# Connectors.net
KiCad netlist of a schematic drawn in Altium Designer
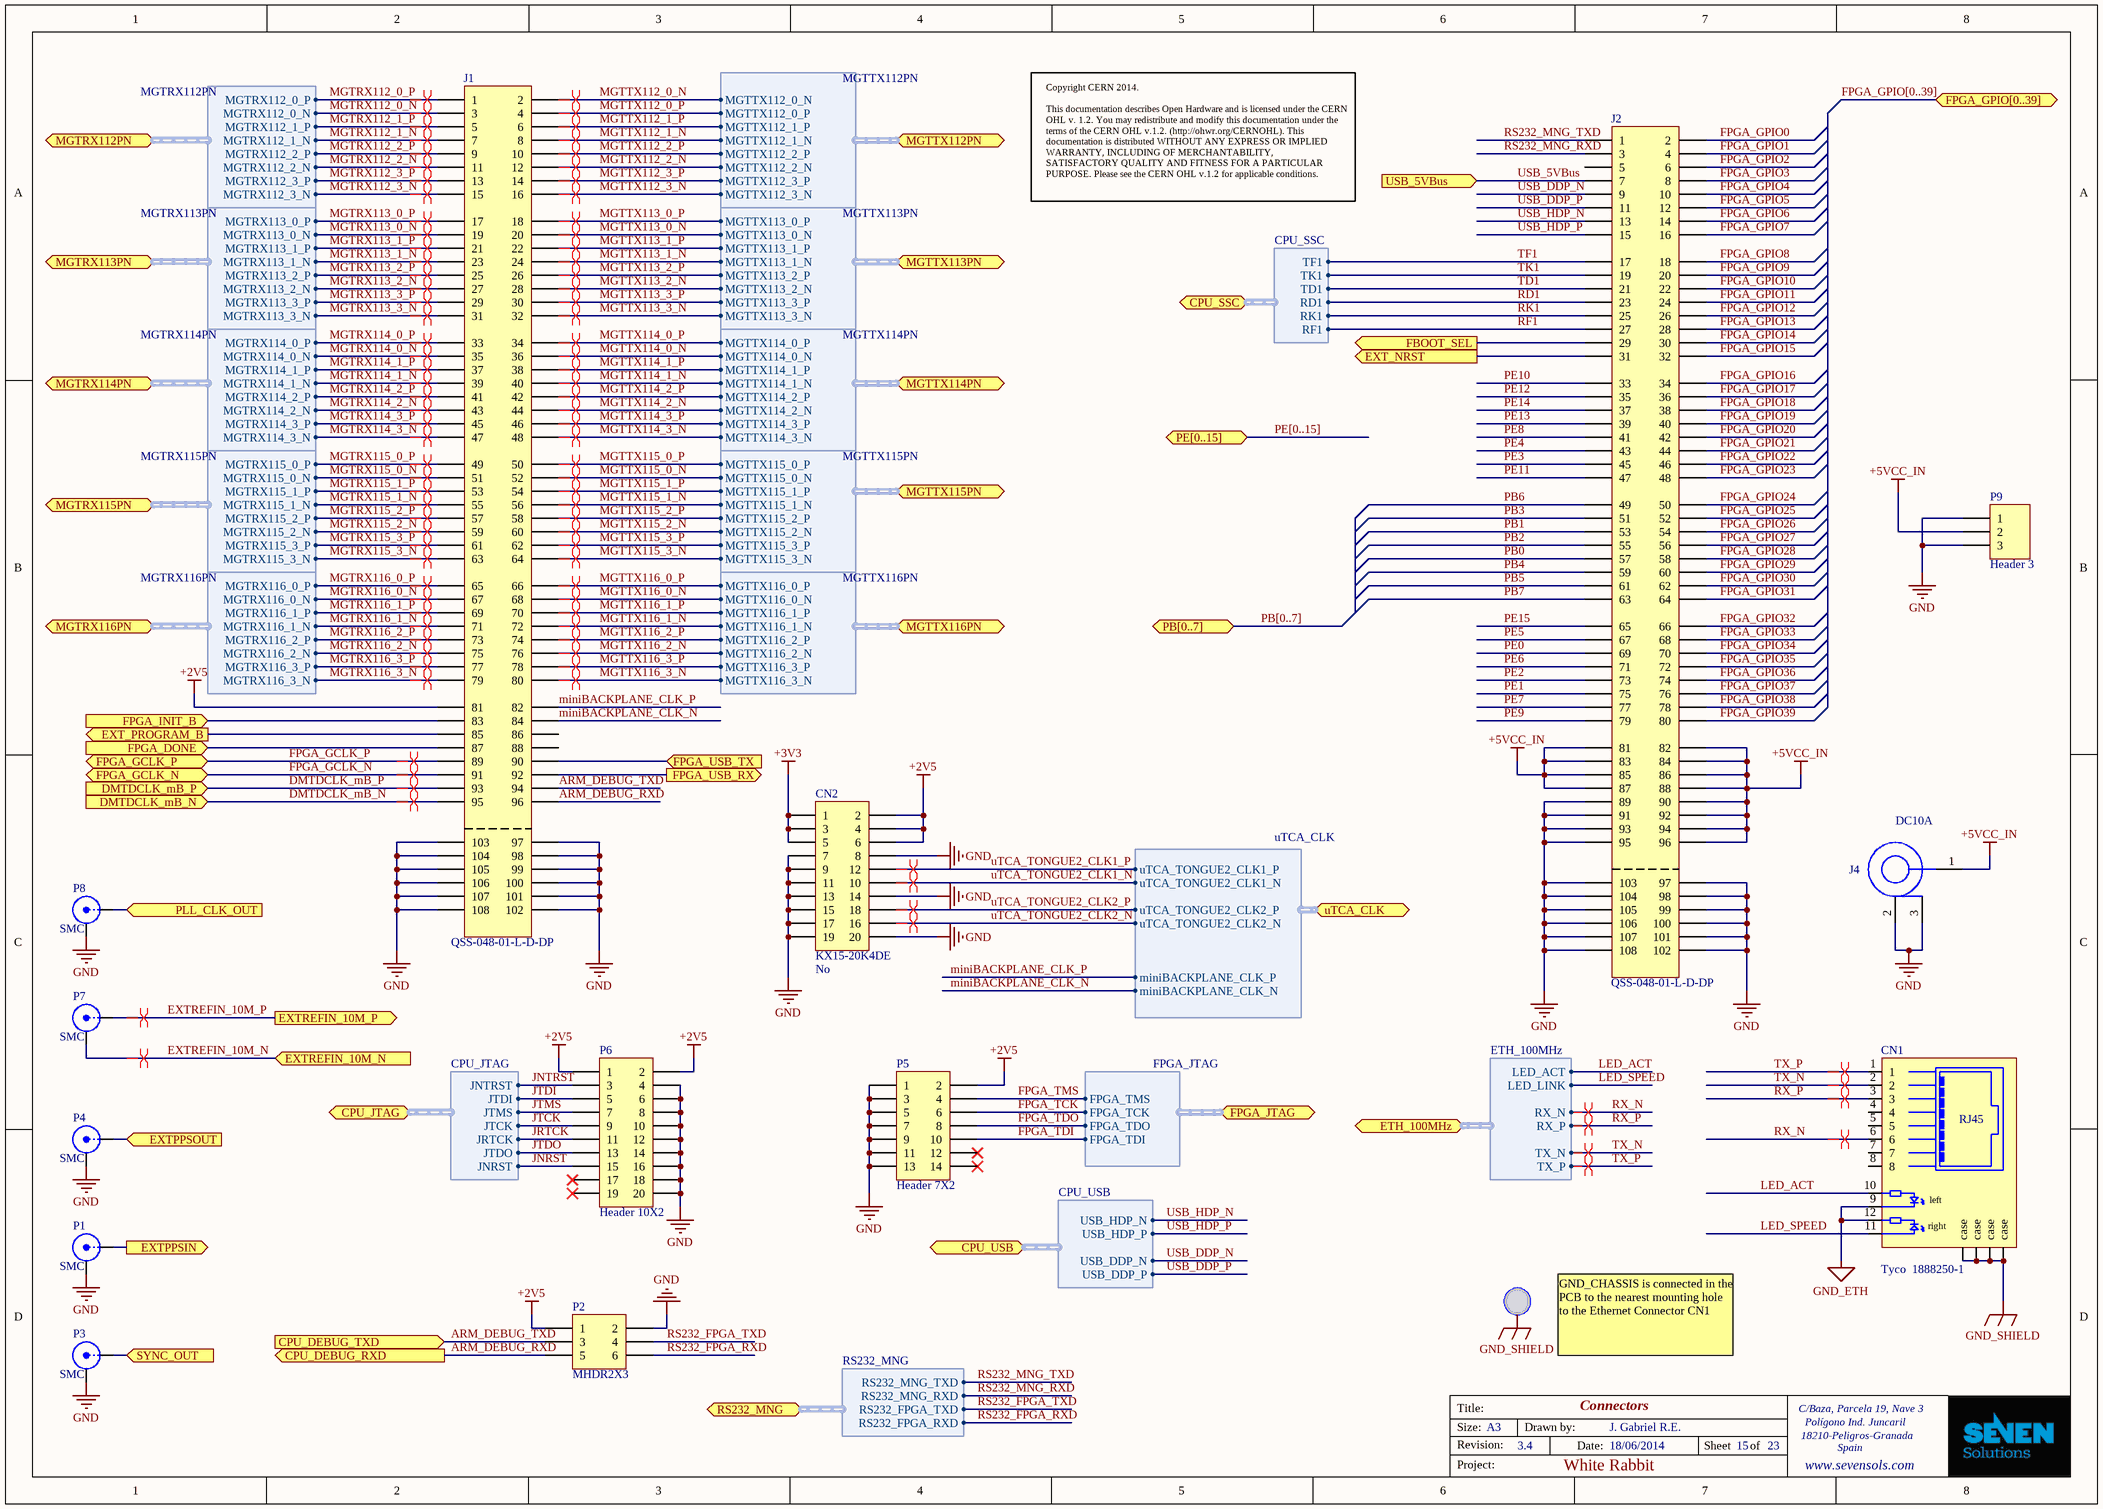
[diagram p0: Connectors.SchDoc]

(export (version "E")
  (design (tool "Eeschema 10.0.6"))
  (components
    (comp (ref "CN1")
      (value "Tyco  1888250-1")
      (footprint "TYCO_ETHERNET_1888250-1")
      (description "low profile uTCA Ethernet jack (RJ45)")
      (libsource (lib "wr_switch") (part "CON_ETHERNET_TYCO_1888250-1"))
    )
    (comp (ref "CN2")
      (value "KX15-20K4DE")
      (footprint "JAE_KX15_20P")
      (description "multipin B2B connector (plug)")
      (fields (field (name "MOUNTED") "No"))
      (libsource (lib "wr_switch") (part "KX15_20p"))
    )
    (comp (ref "J1")
      (value "QSS-048-01-L-D-DP")
      (footprint "QSS-048-01-X-D-DP-A")
      (libsource (lib "wr_switch") (part "QSS-048-01-L-D-DP"))
    )
    (comp (ref "J2")
      (value "QSS-048-01-L-D-DP")
      (footprint "QSS-048-01-X-D-DP-A")
      (description "High Speed Ground Plane Header")
      (libsource (lib "wr_switch") (part "QSS-048-01-L-D-DP"))
    )
    (comp (ref "J4")
      (value "DC10A")
      (footprint "dc-10")
      (description "Power Jack 5A @ 12V")
      (libsource (lib "wr_switch") (part "PWR_JACK"))
    )
    (comp (ref "P1")
      (value "SMC")
      (footprint "SMB_V-RJ45")
      (description "SMB Straight Connector")
      (fields (field (name "PUBLISHER") "Altium Limited"))
      (libsource (lib "Miscellaneous Connectors") (part "SMB"))
    )
    (comp (ref "P2")
      (value "MHDR2X3")
      (footprint "7S_WR:HDR2x3_M22")
      (description "SMD Header, 3-Pin, Dual row, 2.54mm pitch")
      (libsource (lib "Miscellaneous Connectors") (part "MHDR2X3"))
    )
    (comp (ref "P3")
      (value "SMC")
      (footprint "SMB_V-RJ45")
      (description "SMB Straight Connector")
      (fields (field (name "PUBLISHER") "Altium Limited"))
      (libsource (lib "Miscellaneous Connectors") (part "SMB"))
    )
    (comp (ref "P4")
      (value "SMC")
      (footprint "SMB_V-RJ45")
      (description "SMB Straight Connector")
      (fields (field (name "PUBLISHER") "Altium Limited"))
      (libsource (lib "Miscellaneous Connectors") (part "SMB"))
    )
    (comp (ref "P5")
      (value "Header 7X2")
      (footprint "7S_WR:CONN_HDR_SMD_2mm_2x7")
      (description "Header, 7-Pin, Dual row, 2.0 mm pitch")
      (fields (field (name "PUBLISHER") "Altium Limited"))
      (libsource (lib "Miscellaneous Connectors") (part "Header 7X2"))
    )
    (comp (ref "P6")
      (value "Header 10X2")
      (footprint "7S_WR:HDR2X10_SBH11")
      (description "Header, 10-Pin, Dual row, 2.54mm pitch")
      (fields (field (name "MANUFACTURER") "Sullis Connectors") (field (name "PUBLISHER") "Altium Limited"))
      (libsource (lib "Miscellaneous Connectors") (part "Header 10X2"))
    )
    (comp (ref "P7")
      (value "SMC")
      (footprint "SMB_V-RJ45")
      (description "SMB Straight Connector")
      (fields (field (name "PUBLISHER") "Altium Limited"))
      (libsource (lib "Miscellaneous Connectors") (part "SMB"))
    )
    (comp (ref "P8")
      (value "SMC")
      (footprint "SMB_V-RJ45")
      (description "SMB Straight Connector")
      (fields (field (name "PUBLISHER") "Altium Limited"))
      (libsource (lib "Miscellaneous Connectors") (part "SMB"))
    )
    (comp (ref "P9")
      (value "Header 3")
      (footprint "7S_WR:HDR1x3_BG055")
      (description "Header, 3-Pin")
      (fields (field (name "PUBLISHER") "Altium Limited"))
      (libsource (lib "Miscellaneous Connectors") (part "Header 3"))
    )
  )
  (nets
    (net (code "18") (name "+2V5") (class "Default")
      (node (ref "CN2") (pin "2") (pinfunction "2_2") (pintype "passive"))
      (node (ref "CN2") (pin "4") (pinfunction "4_4") (pintype "passive"))
      (node (ref "CN2") (pin "6") (pinfunction "6_6") (pintype "passive"))
      (node (ref "J1") (pin "81") (pinfunction "81_81") (pintype "passive"))
      (node (ref "P2") (pin "1") (pinfunction "1_1") (pintype "passive"))
      (node (ref "P5") (pin "2") (pinfunction "2_2") (pintype "passive"))
      (node (ref "P6") (pin "1") (pinfunction "1_1") (pintype "passive"))
      (node (ref "P6") (pin "2") (pinfunction "2_2") (pintype "passive"))
    )
    (net (code "19") (name "+3V3") (class "Default")
      (node (ref "CN2") (pin "1") (pinfunction "1_1") (pintype "passive"))
      (node (ref "CN2") (pin "3") (pinfunction "3_3") (pintype "passive"))
      (node (ref "CN2") (pin "5") (pinfunction "5_5") (pintype "passive"))
    )
    (net (code "20") (name "+5VCC_IN") (class "Default")
      (node (ref "J2") (pin "81") (pinfunction "81_81") (pintype "passive"))
      (node (ref "J2") (pin "82") (pinfunction "82_82") (pintype "passive"))
      (node (ref "J2") (pin "83") (pinfunction "83_83") (pintype "passive"))
      (node (ref "J2") (pin "84") (pinfunction "84_84") (pintype "passive"))
      (node (ref "J2") (pin "85") (pinfunction "85_85") (pintype "passive"))
      (node (ref "J2") (pin "86") (pinfunction "86_86") (pintype "passive"))
      (node (ref "J2") (pin "87") (pinfunction "87_87") (pintype "passive"))
      (node (ref "J2") (pin "88") (pinfunction "88_88") (pintype "passive"))
      (node (ref "J2") (pin "90") (pinfunction "90_90") (pintype "passive"))
      (node (ref "J2") (pin "92") (pinfunction "92_92") (pintype "passive"))
      (node (ref "J2") (pin "94") (pinfunction "94_94") (pintype "passive"))
      (node (ref "J2") (pin "96") (pinfunction "96_96") (pintype "passive"))
      (node (ref "J4") (pin "1") (pinfunction "P1_1") (pintype "power_in"))
      (node (ref "P9") (pin "2") (pinfunction "2_2") (pintype "passive"))
    )
    (net (code "21") (name "/ARM_DEBUG_RXD") (class "Default")
      (node (ref "J1") (pin "96") (pinfunction "96_96") (pintype "passive"))
      (node (ref "P2") (pin "5") (pinfunction "5_5") (pintype "passive"))
    )
    (net (code "22") (name "/ARM_DEBUG_TXD") (class "Default")
      (node (ref "J1") (pin "94") (pinfunction "94_94") (pintype "passive"))
      (node (ref "P2") (pin "3") (pinfunction "3_3") (pintype "passive"))
    )
    (net (code "23") (name "/DMTDCLK_mB_N") (class "Default")
      (node (ref "J1") (pin "95") (pinfunction "95_95") (pintype "passive"))
    )
    (net (code "24") (name "/DMTDCLK_mB_P") (class "Default")
      (node (ref "J1") (pin "93") (pinfunction "93_93") (pintype "passive"))
    )
    (net (code "25") (name "/EXTPPSIN") (class "Default")
      (node (ref "P1") (pin "1") (pinfunction "X_1") (pintype "passive"))
    )
    (net (code "26") (name "/EXTPPSOUT") (class "Default")
      (node (ref "P4") (pin "1") (pinfunction "X_1") (pintype "passive"))
    )
    (net (code "27") (name "/EXTREFIN_10M_N") (class "Default")
      (node (ref "P7") (pin "2") (pinfunction "Y_2") (pintype "passive"))
    )
    (net (code "28") (name "/EXTREFIN_10M_P") (class "Default")
      (node (ref "P7") (pin "1") (pinfunction "X_1") (pintype "passive"))
    )
    (net (code "29") (name "/EXT_NRST") (class "Default")
      (node (ref "J2") (pin "31") (pinfunction "31_31") (pintype "passive"))
    )
    (net (code "30") (name "/EXT_PROGRAM_B") (class "Default")
      (node (ref "J1") (pin "85") (pinfunction "85_85") (pintype "passive"))
    )
    (net (code "31") (name "/FBOOT_SEL") (class "Default")
      (node (ref "J2") (pin "29") (pinfunction "29_29") (pintype "passive"))
    )
    (net (code "32") (name "/FPGA_DONE") (class "Default")
      (node (ref "J1") (pin "87") (pinfunction "87_87") (pintype "passive"))
    )
    (net (code "33") (name "/FPGA_GCLK_N") (class "Default")
      (node (ref "J1") (pin "91") (pinfunction "91_91") (pintype "passive"))
    )
    (net (code "34") (name "/FPGA_GCLK_P") (class "Default")
      (node (ref "J1") (pin "89") (pinfunction "89_89") (pintype "passive"))
    )
    (net (code "35") (name "/FPGA_GPIO0") (class "Default")
      (node (ref "J2") (pin "2") (pinfunction "2_2") (pintype "passive"))
    )
    (net (code "36") (name "/FPGA_GPIO1") (class "Default")
      (node (ref "J2") (pin "4") (pinfunction "4_4") (pintype "passive"))
    )
    (net (code "37") (name "/FPGA_GPIO2") (class "Default")
      (node (ref "J2") (pin "6") (pinfunction "6_6") (pintype "passive"))
    )
    (net (code "38") (name "/FPGA_GPIO3") (class "Default")
      (node (ref "J2") (pin "8") (pinfunction "8_8") (pintype "passive"))
    )
    (net (code "39") (name "/FPGA_GPIO4") (class "Default")
      (node (ref "J2") (pin "10") (pinfunction "10_10") (pintype "passive"))
    )
    (net (code "40") (name "/FPGA_GPIO5") (class "Default")
      (node (ref "J2") (pin "12") (pinfunction "12_12") (pintype "passive"))
    )
    (net (code "41") (name "/FPGA_GPIO6") (class "Default")
      (node (ref "J2") (pin "14") (pinfunction "14_14") (pintype "passive"))
    )
    (net (code "42") (name "/FPGA_GPIO7") (class "Default")
      (node (ref "J2") (pin "16") (pinfunction "16_16") (pintype "passive"))
    )
    (net (code "43") (name "/FPGA_GPIO8") (class "Default")
      (node (ref "J2") (pin "18") (pinfunction "18_18") (pintype "passive"))
    )
    (net (code "44") (name "/FPGA_GPIO9") (class "Default")
      (node (ref "J2") (pin "20") (pinfunction "20_20") (pintype "passive"))
    )
    (net (code "45") (name "/FPGA_GPIO10") (class "Default")
      (node (ref "J2") (pin "22") (pinfunction "22_22") (pintype "passive"))
    )
    (net (code "46") (name "/FPGA_GPIO11") (class "Default")
      (node (ref "J2") (pin "24") (pinfunction "24_24") (pintype "passive"))
    )
    (net (code "47") (name "/FPGA_GPIO12") (class "Default")
      (node (ref "J2") (pin "26") (pinfunction "26_26") (pintype "passive"))
    )
    (net (code "48") (name "/FPGA_GPIO13") (class "Default")
      (node (ref "J2") (pin "28") (pinfunction "28_28") (pintype "passive"))
    )
    (net (code "49") (name "/FPGA_GPIO14") (class "Default")
      (node (ref "J2") (pin "30") (pinfunction "30_30") (pintype "passive"))
    )
    (net (code "50") (name "/FPGA_GPIO15") (class "Default")
      (node (ref "J2") (pin "32") (pinfunction "32_32") (pintype "passive"))
    )
    (net (code "51") (name "/FPGA_GPIO16") (class "Default")
      (node (ref "J2") (pin "34") (pinfunction "34_34") (pintype "passive"))
    )
    (net (code "52") (name "/FPGA_GPIO17") (class "Default")
      (node (ref "J2") (pin "36") (pinfunction "36_36") (pintype "passive"))
    )
    (net (code "53") (name "/FPGA_GPIO18") (class "Default")
      (node (ref "J2") (pin "38") (pinfunction "38_38") (pintype "passive"))
    )
    (net (code "54") (name "/FPGA_GPIO19") (class "Default")
      (node (ref "J2") (pin "40") (pinfunction "40_40") (pintype "passive"))
    )
    (net (code "55") (name "/FPGA_GPIO20") (class "Default")
      (node (ref "J2") (pin "42") (pinfunction "42_42") (pintype "passive"))
    )
    (net (code "56") (name "/FPGA_GPIO21") (class "Default")
      (node (ref "J2") (pin "44") (pinfunction "44_44") (pintype "passive"))
    )
    (net (code "57") (name "/FPGA_GPIO22") (class "Default")
      (node (ref "J2") (pin "46") (pinfunction "46_46") (pintype "passive"))
    )
    (net (code "58") (name "/FPGA_GPIO23") (class "Default")
      (node (ref "J2") (pin "48") (pinfunction "48_48") (pintype "passive"))
    )
    (net (code "59") (name "/FPGA_GPIO24") (class "Default")
      (node (ref "J2") (pin "50") (pinfunction "50_50") (pintype "passive"))
    )
    (net (code "60") (name "/FPGA_GPIO25") (class "Default")
      (node (ref "J2") (pin "52") (pinfunction "52_52") (pintype "passive"))
    )
    (net (code "61") (name "/FPGA_GPIO26") (class "Default")
      (node (ref "J2") (pin "54") (pinfunction "54_54") (pintype "passive"))
    )
    (net (code "62") (name "/FPGA_GPIO27") (class "Default")
      (node (ref "J2") (pin "56") (pinfunction "56_56") (pintype "passive"))
    )
    (net (code "63") (name "/FPGA_GPIO28") (class "Default")
      (node (ref "J2") (pin "58") (pinfunction "58_58") (pintype "passive"))
    )
    (net (code "64") (name "/FPGA_GPIO29") (class "Default")
      (node (ref "J2") (pin "60") (pinfunction "60_60") (pintype "passive"))
    )
    (net (code "65") (name "/FPGA_GPIO30") (class "Default")
      (node (ref "J2") (pin "62") (pinfunction "62_62") (pintype "passive"))
    )
    (net (code "66") (name "/FPGA_GPIO31") (class "Default")
      (node (ref "J2") (pin "64") (pinfunction "64_64") (pintype "passive"))
    )
    (net (code "67") (name "/FPGA_GPIO32") (class "Default")
      (node (ref "J2") (pin "66") (pinfunction "66_66") (pintype "passive"))
    )
    (net (code "68") (name "/FPGA_GPIO33") (class "Default")
      (node (ref "J2") (pin "68") (pinfunction "68_68") (pintype "passive"))
    )
    (net (code "69") (name "/FPGA_GPIO34") (class "Default")
      (node (ref "J2") (pin "70") (pinfunction "70_70") (pintype "passive"))
    )
    (net (code "70") (name "/FPGA_GPIO35") (class "Default")
      (node (ref "J2") (pin "72") (pinfunction "72_72") (pintype "passive"))
    )
    (net (code "71") (name "/FPGA_GPIO36") (class "Default")
      (node (ref "J2") (pin "74") (pinfunction "74_74") (pintype "passive"))
    )
    (net (code "72") (name "/FPGA_GPIO37") (class "Default")
      (node (ref "J2") (pin "76") (pinfunction "76_76") (pintype "passive"))
    )
    (net (code "73") (name "/FPGA_GPIO38") (class "Default")
      (node (ref "J2") (pin "78") (pinfunction "78_78") (pintype "passive"))
    )
    (net (code "74") (name "/FPGA_GPIO39") (class "Default")
      (node (ref "J2") (pin "80") (pinfunction "80_80") (pintype "passive"))
    )
    (net (code "76") (name "/FPGA_INIT_B") (class "Default")
      (node (ref "J1") (pin "83") (pinfunction "83_83") (pintype "passive"))
    )
    (net (code "77") (name "/FPGA_TCK") (class "Default")
      (node (ref "P5") (pin "6") (pinfunction "6_6") (pintype "passive"))
    )
    (net (code "78") (name "/FPGA_TDI") (class "Default")
      (node (ref "P5") (pin "10") (pinfunction "10_10") (pintype "passive"))
    )
    (net (code "79") (name "/FPGA_TDO") (class "Default")
      (node (ref "P5") (pin "8") (pinfunction "8_8") (pintype "passive"))
    )
    (net (code "80") (name "/FPGA_TMS") (class "Default")
      (node (ref "P5") (pin "4") (pinfunction "4_4") (pintype "passive"))
    )
    (net (code "81") (name "/FPGA_USB_RX") (class "Default")
      (node (ref "J1") (pin "92") (pinfunction "92_92") (pintype "passive"))
    )
    (net (code "82") (name "/FPGA_USB_TX") (class "Default")
      (node (ref "J1") (pin "90") (pinfunction "90_90") (pintype "passive"))
    )
    (net (code "83") (name "/JNRST") (class "Default")
      (node (ref "P6") (pin "15") (pinfunction "15_15") (pintype "passive"))
    )
    (net (code "84") (name "/JNTRST") (class "Default")
      (node (ref "P6") (pin "3") (pinfunction "3_3") (pintype "passive"))
    )
    (net (code "85") (name "/JRTCK") (class "Default")
      (node (ref "P6") (pin "11") (pinfunction "11_11") (pintype "passive"))
    )
    (net (code "86") (name "/JTCK") (class "Default")
      (node (ref "P6") (pin "9") (pinfunction "9_9") (pintype "passive"))
    )
    (net (code "87") (name "/JTDI") (class "Default")
      (node (ref "P6") (pin "5") (pinfunction "5_5") (pintype "passive"))
    )
    (net (code "88") (name "/JTDO") (class "Default")
      (node (ref "P6") (pin "13") (pinfunction "13_13") (pintype "passive"))
    )
    (net (code "89") (name "/JTMS") (class "Default")
      (node (ref "P6") (pin "7") (pinfunction "7_7") (pintype "passive"))
    )
    (net (code "90") (name "/LED_ACT") (class "Default")
      (node (ref "CN1") (pin "10") (pinfunction "D1_10") (pintype "passive"))
    )
    (net (code "91") (name "/LED_SPEED") (class "Default")
      (node (ref "CN1") (pin "11") (pinfunction "D4_11") (pintype "passive"))
    )
    (net (code "92") (name "/MGTRX112_0_N") (class "Default")
      (node (ref "J1") (pin "3") (pinfunction "3_3") (pintype "passive"))
    )
    (net (code "93") (name "/MGTRX112_0_P") (class "Default")
      (node (ref "J1") (pin "1") (pinfunction "1_1") (pintype "passive"))
    )
    (net (code "94") (name "/MGTRX112_1_N") (class "Default")
      (node (ref "J1") (pin "7") (pinfunction "7_7") (pintype "passive"))
    )
    (net (code "95") (name "/MGTRX112_1_P") (class "Default")
      (node (ref "J1") (pin "5") (pinfunction "5_5") (pintype "passive"))
    )
    (net (code "96") (name "/MGTRX112_2_N") (class "Default")
      (node (ref "J1") (pin "11") (pinfunction "11_11") (pintype "passive"))
    )
    (net (code "97") (name "/MGTRX112_2_P") (class "Default")
      (node (ref "J1") (pin "9") (pinfunction "9_9") (pintype "passive"))
    )
    (net (code "98") (name "/MGTRX112_3_N") (class "Default")
      (node (ref "J1") (pin "15") (pinfunction "15_15") (pintype "passive"))
    )
    (net (code "99") (name "/MGTRX112_3_P") (class "Default")
      (node (ref "J1") (pin "13") (pinfunction "13_13") (pintype "passive"))
    )
    (net (code "100") (name "/MGTRX113_0_N") (class "Default")
      (node (ref "J1") (pin "19") (pinfunction "19_19") (pintype "passive"))
    )
    (net (code "101") (name "/MGTRX113_0_P") (class "Default")
      (node (ref "J1") (pin "17") (pinfunction "17_17") (pintype "passive"))
    )
    (net (code "102") (name "/MGTRX113_1_N") (class "Default")
      (node (ref "J1") (pin "23") (pinfunction "23_23") (pintype "passive"))
    )
    (net (code "103") (name "/MGTRX113_1_P") (class "Default")
      (node (ref "J1") (pin "21") (pinfunction "21_21") (pintype "passive"))
    )
    (net (code "104") (name "/MGTRX113_2_N") (class "Default")
      (node (ref "J1") (pin "27") (pinfunction "27_27") (pintype "passive"))
    )
    (net (code "105") (name "/MGTRX113_2_P") (class "Default")
      (node (ref "J1") (pin "25") (pinfunction "25_25") (pintype "passive"))
    )
    (net (code "106") (name "/MGTRX113_3_N") (class "Default")
      (node (ref "J1") (pin "31") (pinfunction "31_31") (pintype "passive"))
    )
    (net (code "107") (name "/MGTRX113_3_P") (class "Default")
      (node (ref "J1") (pin "29") (pinfunction "29_29") (pintype "passive"))
    )
    (net (code "108") (name "/MGTRX114_0_N") (class "Default")
      (node (ref "J1") (pin "35") (pinfunction "35_35") (pintype "passive"))
    )
    (net (code "109") (name "/MGTRX114_0_P") (class "Default")
      (node (ref "J1") (pin "33") (pinfunction "33_33") (pintype "passive"))
    )
    (net (code "110") (name "/MGTRX114_1_N") (class "Default")
      (node (ref "J1") (pin "39") (pinfunction "39_39") (pintype "passive"))
    )
    (net (code "111") (name "/MGTRX114_1_P") (class "Default")
      (node (ref "J1") (pin "37") (pinfunction "37_37") (pintype "passive"))
    )
    (net (code "112") (name "/MGTRX114_2_N") (class "Default")
      (node (ref "J1") (pin "43") (pinfunction "43_43") (pintype "passive"))
    )
    (net (code "113") (name "/MGTRX114_2_P") (class "Default")
      (node (ref "J1") (pin "41") (pinfunction "41_41") (pintype "passive"))
    )
    (net (code "114") (name "/MGTRX114_3_N") (class "Default")
      (node (ref "J1") (pin "47") (pinfunction "47_47") (pintype "passive"))
    )
    (net (code "115") (name "/MGTRX114_3_P") (class "Default")
      (node (ref "J1") (pin "45") (pinfunction "45_45") (pintype "passive"))
    )
    (net (code "116") (name "/MGTRX115_0_N") (class "Default")
      (node (ref "J1") (pin "51") (pinfunction "51_51") (pintype "passive"))
    )
    (net (code "117") (name "/MGTRX115_0_P") (class "Default")
      (node (ref "J1") (pin "49") (pinfunction "49_49") (pintype "passive"))
    )
    (net (code "118") (name "/MGTRX115_1_N") (class "Default")
      (node (ref "J1") (pin "55") (pinfunction "55_55") (pintype "passive"))
    )
    (net (code "119") (name "/MGTRX115_1_P") (class "Default")
      (node (ref "J1") (pin "53") (pinfunction "53_53") (pintype "passive"))
    )
    (net (code "120") (name "/MGTRX115_2_N") (class "Default")
      (node (ref "J1") (pin "59") (pinfunction "59_59") (pintype "passive"))
    )
    (net (code "121") (name "/MGTRX115_2_P") (class "Default")
      (node (ref "J1") (pin "57") (pinfunction "57_57") (pintype "passive"))
    )
    (net (code "122") (name "/MGTRX115_3_N") (class "Default")
      (node (ref "J1") (pin "63") (pinfunction "63_63") (pintype "passive"))
    )
    (net (code "123") (name "/MGTRX115_3_P") (class "Default")
      (node (ref "J1") (pin "61") (pinfunction "61_61") (pintype "passive"))
    )
    (net (code "124") (name "/MGTRX116_0_N") (class "Default")
      (node (ref "J1") (pin "67") (pinfunction "67_67") (pintype "passive"))
    )
    (net (code "125") (name "/MGTRX116_0_P") (class "Default")
      (node (ref "J1") (pin "65") (pinfunction "65_65") (pintype "passive"))
    )
    (net (code "126") (name "/MGTRX116_1_N") (class "Default")
      (node (ref "J1") (pin "71") (pinfunction "71_71") (pintype "passive"))
    )
    (net (code "127") (name "/MGTRX116_1_P") (class "Default")
      (node (ref "J1") (pin "69") (pinfunction "69_69") (pintype "passive"))
    )
    (net (code "128") (name "/MGTRX116_2_N") (class "Default")
      (node (ref "J1") (pin "75") (pinfunction "75_75") (pintype "passive"))
    )
    (net (code "129") (name "/MGTRX116_2_P") (class "Default")
      (node (ref "J1") (pin "73") (pinfunction "73_73") (pintype "passive"))
    )
    (net (code "130") (name "/MGTRX116_3_N") (class "Default")
      (node (ref "J1") (pin "79") (pinfunction "79_79") (pintype "passive"))
    )
    (net (code "131") (name "/MGTRX116_3_P") (class "Default")
      (node (ref "J1") (pin "77") (pinfunction "77_77") (pintype "passive"))
    )
    (net (code "132") (name "/MGTTX112_0_N") (class "Default")
      (node (ref "J1") (pin "2") (pinfunction "2_2") (pintype "passive"))
    )
    (net (code "133") (name "/MGTTX112_0_P") (class "Default")
      (node (ref "J1") (pin "4") (pinfunction "4_4") (pintype "passive"))
    )
    (net (code "134") (name "/MGTTX112_1_N") (class "Default")
      (node (ref "J1") (pin "8") (pinfunction "8_8") (pintype "passive"))
    )
    (net (code "135") (name "/MGTTX112_1_P") (class "Default")
      (node (ref "J1") (pin "6") (pinfunction "6_6") (pintype "passive"))
    )
    (net (code "136") (name "/MGTTX112_2_N") (class "Default")
      (node (ref "J1") (pin "12") (pinfunction "12_12") (pintype "passive"))
    )
    (net (code "137") (name "/MGTTX112_2_P") (class "Default")
      (node (ref "J1") (pin "10") (pinfunction "10_10") (pintype "passive"))
    )
    (net (code "138") (name "/MGTTX112_3_N") (class "Default")
      (node (ref "J1") (pin "16") (pinfunction "16_16") (pintype "passive"))
    )
    (net (code "139") (name "/MGTTX112_3_P") (class "Default")
      (node (ref "J1") (pin "14") (pinfunction "14_14") (pintype "passive"))
    )
    (net (code "140") (name "/MGTTX113_0_N") (class "Default")
      (node (ref "J1") (pin "20") (pinfunction "20_20") (pintype "passive"))
    )
    (net (code "141") (name "/MGTTX113_0_P") (class "Default")
      (node (ref "J1") (pin "18") (pinfunction "18_18") (pintype "passive"))
    )
    (net (code "142") (name "/MGTTX113_1_N") (class "Default")
      (node (ref "J1") (pin "24") (pinfunction "24_24") (pintype "passive"))
    )
    (net (code "143") (name "/MGTTX113_1_P") (class "Default")
      (node (ref "J1") (pin "22") (pinfunction "22_22") (pintype "passive"))
    )
    (net (code "144") (name "/MGTTX113_2_N") (class "Default")
      (node (ref "J1") (pin "28") (pinfunction "28_28") (pintype "passive"))
    )
    (net (code "145") (name "/MGTTX113_2_P") (class "Default")
      (node (ref "J1") (pin "26") (pinfunction "26_26") (pintype "passive"))
    )
    (net (code "146") (name "/MGTTX113_3_N") (class "Default")
      (node (ref "J1") (pin "32") (pinfunction "32_32") (pintype "passive"))
    )
    (net (code "147") (name "/MGTTX113_3_P") (class "Default")
      (node (ref "J1") (pin "30") (pinfunction "30_30") (pintype "passive"))
    )
    (net (code "148") (name "/MGTTX114_0_N") (class "Default")
      (node (ref "J1") (pin "36") (pinfunction "36_36") (pintype "passive"))
    )
    (net (code "149") (name "/MGTTX114_0_P") (class "Default")
      (node (ref "J1") (pin "34") (pinfunction "34_34") (pintype "passive"))
    )
    (net (code "150") (name "/MGTTX114_1_N") (class "Default")
      (node (ref "J1") (pin "40") (pinfunction "40_40") (pintype "passive"))
    )
    (net (code "151") (name "/MGTTX114_1_P") (class "Default")
      (node (ref "J1") (pin "38") (pinfunction "38_38") (pintype "passive"))
    )
    (net (code "152") (name "/MGTTX114_2_N") (class "Default")
      (node (ref "J1") (pin "44") (pinfunction "44_44") (pintype "passive"))
    )
    (net (code "153") (name "/MGTTX114_2_P") (class "Default")
      (node (ref "J1") (pin "42") (pinfunction "42_42") (pintype "passive"))
    )
    (net (code "154") (name "/MGTTX114_3_N") (class "Default")
      (node (ref "J1") (pin "48") (pinfunction "48_48") (pintype "passive"))
    )
    (net (code "155") (name "/MGTTX114_3_P") (class "Default")
      (node (ref "J1") (pin "46") (pinfunction "46_46") (pintype "passive"))
    )
    (net (code "156") (name "/MGTTX115_0_N") (class "Default")
      (node (ref "J1") (pin "52") (pinfunction "52_52") (pintype "passive"))
    )
    (net (code "157") (name "/MGTTX115_0_P") (class "Default")
      (node (ref "J1") (pin "50") (pinfunction "50_50") (pintype "passive"))
    )
    (net (code "158") (name "/MGTTX115_1_N") (class "Default")
      (node (ref "J1") (pin "56") (pinfunction "56_56") (pintype "passive"))
    )
    (net (code "159") (name "/MGTTX115_1_P") (class "Default")
      (node (ref "J1") (pin "54") (pinfunction "54_54") (pintype "passive"))
    )
    (net (code "160") (name "/MGTTX115_2_N") (class "Default")
      (node (ref "J1") (pin "60") (pinfunction "60_60") (pintype "passive"))
    )
    (net (code "161") (name "/MGTTX115_2_P") (class "Default")
      (node (ref "J1") (pin "58") (pinfunction "58_58") (pintype "passive"))
    )
    (net (code "162") (name "/MGTTX115_3_N") (class "Default")
      (node (ref "J1") (pin "64") (pinfunction "64_64") (pintype "passive"))
    )
    (net (code "163") (name "/MGTTX115_3_P") (class "Default")
      (node (ref "J1") (pin "62") (pinfunction "62_62") (pintype "passive"))
    )
    (net (code "164") (name "/MGTTX116_0_N") (class "Default")
      (node (ref "J1") (pin "68") (pinfunction "68_68") (pintype "passive"))
    )
    (net (code "165") (name "/MGTTX116_0_P") (class "Default")
      (node (ref "J1") (pin "66") (pinfunction "66_66") (pintype "passive"))
    )
    (net (code "166") (name "/MGTTX116_1_N") (class "Default")
      (node (ref "J1") (pin "72") (pinfunction "72_72") (pintype "passive"))
    )
    (net (code "167") (name "/MGTTX116_1_P") (class "Default")
      (node (ref "J1") (pin "70") (pinfunction "70_70") (pintype "passive"))
    )
    (net (code "168") (name "/MGTTX116_2_N") (class "Default")
      (node (ref "J1") (pin "76") (pinfunction "76_76") (pintype "passive"))
    )
    (net (code "169") (name "/MGTTX116_2_P") (class "Default")
      (node (ref "J1") (pin "74") (pinfunction "74_74") (pintype "passive"))
    )
    (net (code "170") (name "/MGTTX116_3_N") (class "Default")
      (node (ref "J1") (pin "80") (pinfunction "80_80") (pintype "passive"))
    )
    (net (code "171") (name "/MGTTX116_3_P") (class "Default")
      (node (ref "J1") (pin "78") (pinfunction "78_78") (pintype "passive"))
    )
    (net (code "172") (name "/PB0") (class "Default")
      (node (ref "J2") (pin "57") (pinfunction "57_57") (pintype "passive"))
    )
    (net (code "173") (name "/PB1") (class "Default")
      (node (ref "J2") (pin "53") (pinfunction "53_53") (pintype "passive"))
    )
    (net (code "174") (name "/PB2") (class "Default")
      (node (ref "J2") (pin "55") (pinfunction "55_55") (pintype "passive"))
    )
    (net (code "175") (name "/PB3") (class "Default")
      (node (ref "J2") (pin "51") (pinfunction "51_51") (pintype "passive"))
    )
    (net (code "176") (name "/PB4") (class "Default")
      (node (ref "J2") (pin "59") (pinfunction "59_59") (pintype "passive"))
    )
    (net (code "177") (name "/PB5") (class "Default")
      (node (ref "J2") (pin "61") (pinfunction "61_61") (pintype "passive"))
    )
    (net (code "178") (name "/PB6") (class "Default")
      (node (ref "J2") (pin "49") (pinfunction "49_49") (pintype "passive"))
    )
    (net (code "179") (name "/PB7") (class "Default")
      (node (ref "J2") (pin "63") (pinfunction "63_63") (pintype "passive"))
    )
    (net (code "181") (name "/PE0") (class "Default")
      (node (ref "J2") (pin "69") (pinfunction "69_69") (pintype "passive"))
    )
    (net (code "182") (name "/PE1") (class "Default")
      (node (ref "J2") (pin "75") (pinfunction "75_75") (pintype "passive"))
    )
    (net (code "183") (name "/PE2") (class "Default")
      (node (ref "J2") (pin "73") (pinfunction "73_73") (pintype "passive"))
    )
    (net (code "184") (name "/PE3") (class "Default")
      (node (ref "J2") (pin "45") (pinfunction "45_45") (pintype "passive"))
    )
    (net (code "185") (name "/PE4") (class "Default")
      (node (ref "J2") (pin "43") (pinfunction "43_43") (pintype "passive"))
    )
    (net (code "186") (name "/PE5") (class "Default")
      (node (ref "J2") (pin "67") (pinfunction "67_67") (pintype "passive"))
    )
    (net (code "187") (name "/PE6") (class "Default")
      (node (ref "J2") (pin "71") (pinfunction "71_71") (pintype "passive"))
    )
    (net (code "188") (name "/PE7") (class "Default")
      (node (ref "J2") (pin "77") (pinfunction "77_77") (pintype "passive"))
    )
    (net (code "189") (name "/PE8") (class "Default")
      (node (ref "J2") (pin "41") (pinfunction "41_41") (pintype "passive"))
    )
    (net (code "190") (name "/PE9") (class "Default")
      (node (ref "J2") (pin "79") (pinfunction "79_79") (pintype "passive"))
    )
    (net (code "191") (name "/PE10") (class "Default")
      (node (ref "J2") (pin "33") (pinfunction "33_33") (pintype "passive"))
    )
    (net (code "192") (name "/PE11") (class "Default")
      (node (ref "J2") (pin "47") (pinfunction "47_47") (pintype "passive"))
    )
    (net (code "193") (name "/PE12") (class "Default")
      (node (ref "J2") (pin "35") (pinfunction "35_35") (pintype "passive"))
    )
    (net (code "194") (name "/PE13") (class "Default")
      (node (ref "J2") (pin "39") (pinfunction "39_39") (pintype "passive"))
    )
    (net (code "195") (name "/PE14") (class "Default")
      (node (ref "J2") (pin "37") (pinfunction "37_37") (pintype "passive"))
    )
    (net (code "196") (name "/PE15") (class "Default")
      (node (ref "J2") (pin "65") (pinfunction "65_65") (pintype "passive"))
    )
    (net (code "198") (name "/PLL_CLK_OUT") (class "Default")
      (node (ref "P8") (pin "1") (pinfunction "X_1") (pintype "passive"))
    )
    (net (code "199") (name "/RD1") (class "Default")
      (node (ref "J2") (pin "23") (pinfunction "23_23") (pintype "passive"))
    )
    (net (code "200") (name "/RF1") (class "Default")
      (node (ref "J2") (pin "27") (pinfunction "27_27") (pintype "passive"))
    )
    (net (code "201") (name "/RK1") (class "Default")
      (node (ref "J2") (pin "25") (pinfunction "25_25") (pintype "passive"))
    )
    (net (code "202") (name "/RS232_FPGA_RXD") (class "Default")
      (node (ref "P2") (pin "6") (pinfunction "6_6") (pintype "passive"))
    )
    (net (code "203") (name "/RS232_FPGA_TXD") (class "Default")
      (node (ref "P2") (pin "4") (pinfunction "4_4") (pintype "passive"))
    )
    (net (code "204") (name "/RS232_MNG_RXD") (class "Default")
      (node (ref "J2") (pin "3") (pinfunction "3_3") (pintype "passive"))
    )
    (net (code "205") (name "/RS232_MNG_TXD") (class "Default")
      (node (ref "J2") (pin "1") (pinfunction "1_1") (pintype "passive"))
    )
    (net (code "206") (name "/RX_N") (class "Default")
      (node (ref "CN1") (pin "6") (pinfunction "6_6") (pintype "passive"))
    )
    (net (code "207") (name "/RX_P") (class "Default")
      (node (ref "CN1") (pin "3") (pinfunction "3_3") (pintype "passive"))
    )
    (net (code "208") (name "/SYNC_OUT") (class "Default")
      (node (ref "P3") (pin "1") (pinfunction "X_1") (pintype "passive"))
    )
    (net (code "209") (name "/TD1") (class "Default")
      (node (ref "J2") (pin "21") (pinfunction "21_21") (pintype "passive"))
    )
    (net (code "210") (name "/TF1") (class "Default")
      (node (ref "J2") (pin "17") (pinfunction "17_17") (pintype "passive"))
    )
    (net (code "211") (name "/TK1") (class "Default")
      (node (ref "J2") (pin "19") (pinfunction "19_19") (pintype "passive"))
    )
    (net (code "212") (name "/TX_N") (class "Default")
      (node (ref "CN1") (pin "2") (pinfunction "2_2") (pintype "passive"))
    )
    (net (code "213") (name "/TX_P") (class "Default")
      (node (ref "CN1") (pin "1") (pinfunction "1_1") (pintype "passive"))
    )
    (net (code "214") (name "/USB_5VBus") (class "Default")
      (node (ref "J2") (pin "7") (pinfunction "7_7") (pintype "passive"))
    )
    (net (code "215") (name "/USB_DDP_N") (class "Default")
      (node (ref "J2") (pin "9") (pinfunction "9_9") (pintype "passive"))
    )
    (net (code "216") (name "/USB_DDP_P") (class "Default")
      (node (ref "J2") (pin "11") (pinfunction "11_11") (pintype "passive"))
    )
    (net (code "217") (name "/USB_HDP_N") (class "Default")
      (node (ref "J2") (pin "13") (pinfunction "13_13") (pintype "passive"))
    )
    (net (code "218") (name "/USB_HDP_P") (class "Default")
      (node (ref "J2") (pin "15") (pinfunction "15_15") (pintype "passive"))
    )
    (net (code "219") (name "/miniBACKPLANE_CLK_N") (class "Default")
      (node (ref "J1") (pin "84") (pinfunction "84_84") (pintype "passive"))
    )
    (net (code "220") (name "/miniBACKPLANE_CLK_P") (class "Default")
      (node (ref "J1") (pin "82") (pinfunction "82_82") (pintype "passive"))
    )
    (net (code "221") (name "/uTCA_TONGUE2_CLK1_N") (class "Default")
      (node (ref "CN2") (pin "10") (pinfunction "10_10") (pintype "passive"))
    )
    (net (code "222") (name "/uTCA_TONGUE2_CLK1_P") (class "Default")
      (node (ref "CN2") (pin "12") (pinfunction "12_12") (pintype "passive"))
    )
    (net (code "223") (name "/uTCA_TONGUE2_CLK2_N") (class "Default")
      (node (ref "CN2") (pin "16") (pinfunction "16_16") (pintype "passive"))
    )
    (net (code "224") (name "/uTCA_TONGUE2_CLK2_P") (class "Default")
      (node (ref "CN2") (pin "18") (pinfunction "18_18") (pintype "passive"))
    )
    (net (code "242") (name "GND") (class "Default")
      (node (ref "CN2") (pin "11") (pinfunction "11_11") (pintype "passive"))
      (node (ref "CN2") (pin "13") (pinfunction "13_13") (pintype "passive"))
      (node (ref "CN2") (pin "14") (pinfunction "14_14") (pintype "passive"))
      (node (ref "CN2") (pin "15") (pinfunction "15_15") (pintype "passive"))
      (node (ref "CN2") (pin "17") (pinfunction "17_17") (pintype "passive"))
      (node (ref "CN2") (pin "19") (pinfunction "19_19") (pintype "passive"))
      (node (ref "CN2") (pin "20") (pinfunction "20_20") (pintype "passive"))
      (node (ref "CN2") (pin "7") (pinfunction "7_7") (pintype "passive"))
      (node (ref "CN2") (pin "8") (pinfunction "8_8") (pintype "passive"))
      (node (ref "CN2") (pin "9") (pinfunction "9_9") (pintype "passive"))
      (node (ref "J1") (pin "100") (pinfunction "100_100") (pintype "passive"))
      (node (ref "J1") (pin "101") (pinfunction "101_101") (pintype "passive"))
      (node (ref "J1") (pin "102") (pinfunction "102_102") (pintype "passive"))
      (node (ref "J1") (pin "103") (pinfunction "103_103") (pintype "passive"))
      (node (ref "J1") (pin "104") (pinfunction "104_104") (pintype "passive"))
      (node (ref "J1") (pin "105") (pinfunction "105_105") (pintype "passive"))
      (node (ref "J1") (pin "106") (pinfunction "106_106") (pintype "passive"))
      (node (ref "J1") (pin "107") (pinfunction "107_107") (pintype "passive"))
      (node (ref "J1") (pin "108") (pinfunction "108_108") (pintype "passive"))
      (node (ref "J1") (pin "97") (pinfunction "97_97") (pintype "passive"))
      (node (ref "J1") (pin "98") (pinfunction "98_98") (pintype "passive"))
      (node (ref "J1") (pin "99") (pinfunction "99_99") (pintype "passive"))
      (node (ref "J2") (pin "100") (pinfunction "100_100") (pintype "passive"))
      (node (ref "J2") (pin "101") (pinfunction "101_101") (pintype "passive"))
      (node (ref "J2") (pin "102") (pinfunction "102_102") (pintype "passive"))
      (node (ref "J2") (pin "103") (pinfunction "103_103") (pintype "passive"))
      (node (ref "J2") (pin "104") (pinfunction "104_104") (pintype "passive"))
      (node (ref "J2") (pin "105") (pinfunction "105_105") (pintype "passive"))
      (node (ref "J2") (pin "106") (pinfunction "106_106") (pintype "passive"))
      (node (ref "J2") (pin "107") (pinfunction "107_107") (pintype "passive"))
      (node (ref "J2") (pin "108") (pinfunction "108_108") (pintype "passive"))
      (node (ref "J2") (pin "89") (pinfunction "89_89") (pintype "passive"))
      (node (ref "J2") (pin "91") (pinfunction "91_91") (pintype "passive"))
      (node (ref "J2") (pin "93") (pinfunction "93_93") (pintype "passive"))
      (node (ref "J2") (pin "95") (pinfunction "95_95") (pintype "passive"))
      (node (ref "J2") (pin "97") (pinfunction "97_97") (pintype "passive"))
      (node (ref "J2") (pin "98") (pinfunction "98_98") (pintype "passive"))
      (node (ref "J2") (pin "99") (pinfunction "99_99") (pintype "passive"))
      (node (ref "J4") (pin "2") (pinfunction "P2_2") (pintype "power_in"))
      (node (ref "J4") (pin "3") (pinfunction "P3_3") (pintype "power_in"))
      (node (ref "P1") (pin "2") (pinfunction "Y_2") (pintype "passive"))
      (node (ref "P2") (pin "2") (pinfunction "2_2") (pintype "passive"))
      (node (ref "P3") (pin "2") (pinfunction "Y_2") (pintype "passive"))
      (node (ref "P4") (pin "2") (pinfunction "Y_2") (pintype "passive"))
      (node (ref "P5") (pin "1") (pinfunction "1_1") (pintype "passive"))
      (node (ref "P5") (pin "11") (pinfunction "11_11") (pintype "passive"))
      (node (ref "P5") (pin "13") (pinfunction "13_13") (pintype "passive"))
      (node (ref "P5") (pin "3") (pinfunction "3_3") (pintype "passive"))
      (node (ref "P5") (pin "5") (pinfunction "5_5") (pintype "passive"))
      (node (ref "P5") (pin "7") (pinfunction "7_7") (pintype "passive"))
      (node (ref "P5") (pin "9") (pinfunction "9_9") (pintype "passive"))
      (node (ref "P6") (pin "10") (pinfunction "10_10") (pintype "passive"))
      (node (ref "P6") (pin "12") (pinfunction "12_12") (pintype "passive"))
      (node (ref "P6") (pin "14") (pinfunction "14_14") (pintype "passive"))
      (node (ref "P6") (pin "16") (pinfunction "16_16") (pintype "passive"))
      (node (ref "P6") (pin "18") (pinfunction "18_18") (pintype "passive"))
      (node (ref "P6") (pin "20") (pinfunction "20_20") (pintype "passive"))
      (node (ref "P6") (pin "4") (pinfunction "4_4") (pintype "passive"))
      (node (ref "P6") (pin "6") (pinfunction "6_6") (pintype "passive"))
      (node (ref "P6") (pin "8") (pinfunction "8_8") (pintype "passive"))
      (node (ref "P8") (pin "2") (pinfunction "Y_2") (pintype "passive"))
      (node (ref "P9") (pin "1") (pinfunction "1_1") (pintype "passive"))
      (node (ref "P9") (pin "3") (pinfunction "3_3") (pintype "passive"))
    )
    (net (code "243") (name "GND_ETH") (class "Default")
      (node (ref "CN1") (pin "12") (pinfunction "D3_12") (pintype "passive"))
      (node (ref "CN1") (pin "9") (pinfunction "D2_9") (pintype "passive"))
    )
    (net (code "244") (name "GND_SHIELD") (class "Default")
      (node (ref "CN1") (pin "0") (pinfunction "case_0") (pintype "passive"))
    )
    (net (code "245") (name "unconnected-(CN1-Pad4)") (class "Default")
      (node (ref "CN1") (pin "4") (pinfunction "4_4") (pintype "passive"))
    )
    (net (code "246") (name "unconnected-(CN1-Pad5)") (class "Default")
      (node (ref "CN1") (pin "5") (pinfunction "5_5") (pintype "passive"))
    )
    (net (code "247") (name "unconnected-(CN1-Pad7)") (class "Default")
      (node (ref "CN1") (pin "7") (pinfunction "7_7") (pintype "passive"))
    )
    (net (code "248") (name "unconnected-(CN1-Pad8)") (class "Default")
      (node (ref "CN1") (pin "8") (pinfunction "8_8") (pintype "passive"))
    )
    (net (code "249") (name "unconnected-(J1-Pad86)") (class "Default")
      (node (ref "J1") (pin "86") (pinfunction "86_86") (pintype "passive"))
    )
    (net (code "250") (name "unconnected-(J1-Pad88)") (class "Default")
      (node (ref "J1") (pin "88") (pinfunction "88_88") (pintype "passive"))
    )
    (net (code "251") (name "unconnected-(J2-Pad5)") (class "Default")
      (node (ref "J2") (pin "5") (pinfunction "5_5") (pintype "passive"))
    )
    (net (code "252") (name "unconnected-(P5-Pad12)") (class "Default")
      (node (ref "P5") (pin "12") (pinfunction "12_12") (pintype "passive+no_connect"))
    )
    (net (code "253") (name "unconnected-(P5-Pad14)") (class "Default")
      (node (ref "P5") (pin "14") (pinfunction "14_14") (pintype "passive+no_connect"))
    )
    (net (code "254") (name "unconnected-(P6-Pad17)") (class "Default")
      (node (ref "P6") (pin "17") (pinfunction "17_17") (pintype "passive+no_connect"))
    )
    (net (code "255") (name "unconnected-(P6-Pad19)") (class "Default")
      (node (ref "P6") (pin "19") (pinfunction "19_19") (pintype "passive+no_connect"))
    )
  )
)
